# BM_Input_Stage.net
KiCad netlist of a schematic drawn in Altium Designer
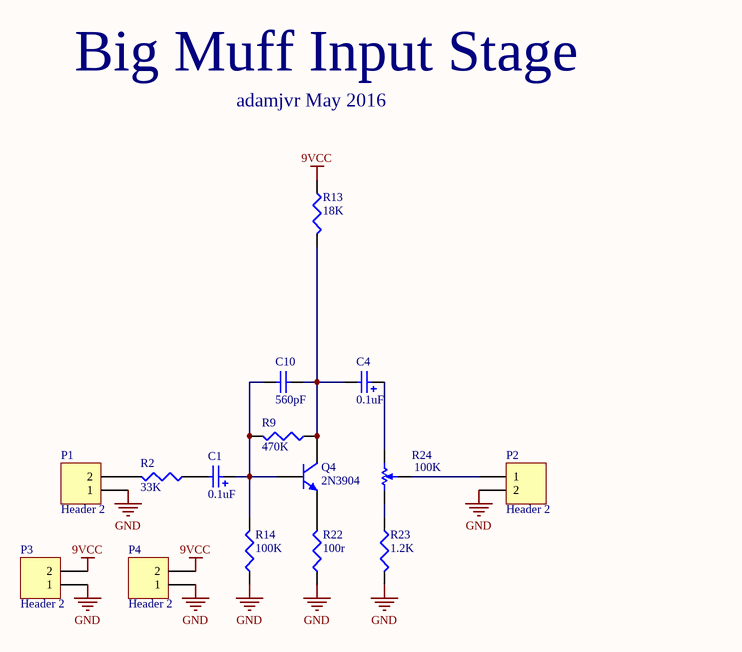
[diagram p0: BM Input Stage.SchDoc]

(export (version "E")
  (design (tool "Eeschema 10.0.6"))
  (components
    (comp (ref "C1")
      (value "0.1uF")
      (footprint "5X12.5mmCAP")
      (description "CAP ALUM 0.1UF 20% 100V RADIAL")
      (fields
        (field (name "MFR") "Nichicon")
        (field (name "TOLERANCE") "20%")
        (field (name "DESIGNER") "Adam Vadala-Roth")
      )
      (libsource (lib "AudioPartLib") (part "UFG2A0R1MDM1TD"))
    )
    (comp (ref "C4")
      (value "0.1uF")
      (footprint "5X12.5mmCAP")
      (description "CAP ALUM 0.1UF 20% 100V RADIAL")
      (fields
        (field (name "MFR") "Nichicon")
        (field (name "TOLERANCE") "20%")
        (field (name "DESIGNER") "Adam Vadala-Roth")
      )
      (libsource (lib "AudioPartLib") (part "UFG2A0R1MDM1TD"))
    )
    (comp (ref "C10")
      (value "560pF")
      (footprint "C0805")
      (fields
        (field (name "MFR") "Samsung-Electro-Mechanics-America,-Inc.")
        (field (name "TOLERANCE") "5%")
        (field (name "VOLTAGE") "50V")
        (field (name "DESIGNER") "Adam Vadala-Roth")
      )
      (libsource (lib "AudioPartLib") (part "CL21C561JBANNNC"))
    )
    (comp (ref "P1")
      (value "Header 2")
      (footprint "HDR1X2")
      (description "Header, 2-Pin")
      (fields (field (name "PUBLISHER") "Altium Limited"))
      (libsource (lib "Miscellaneous Connectors") (part "Header 2"))
    )
    (comp (ref "P2")
      (value "Header 2")
      (footprint "HDR1X2")
      (description "Header, 2-Pin")
      (fields (field (name "PUBLISHER") "Altium Limited"))
      (libsource (lib "") (part "Header 2_1"))
    )
    (comp (ref "P3")
      (value "Header 2")
      (footprint "HDR1X2")
      (description "Header, 2-Pin")
      (fields (field (name "PUBLISHER") "Altium Limited"))
      (libsource (lib "Miscellaneous Connectors") (part "Header 2"))
    )
    (comp (ref "P4")
      (value "Header 2")
      (footprint "HDR1X2")
      (description "Header, 2-Pin")
      (fields (field (name "PUBLISHER") "Altium Limited"))
      (libsource (lib "Miscellaneous Connectors") (part "Header 2"))
    )
    (comp (ref "Q4")
      (value "2N3904")
      (footprint "TO-92A")
      (description "TRANS NPN 40V 0.2A TO-92")
      (fields
        (field (name "MFR") "Fairchild-Semiconductor")
        (field (name "VOLTAGE") "40V")
        (field (name "DESIGNER") "Adam Vadala-Roth")
      )
      (libsource (lib "AudioPartLib") (part "2N3904TF"))
    )
    (comp (ref "R2")
      (value "33K")
      (footprint "R0805")
      (description "RES SMD 33K OHM 1% 1/8W 0805")
      (fields
        (field (name "MFR") "Panasonic-Electronic-Components")
        (field (name "TOLERANCE") "1%")
        (field (name "DESIGNER") "Adam Vadala-Roth")
      )
      (libsource (lib "AudioPartLib") (part "ERJ-6ENF3302V"))
    )
    (comp (ref "R9")
      (value "470K")
      (footprint "R0805")
      (description "RES SMD 470K OHM 1% 1/8W 0805")
      (fields
        (field (name "MFR") "Panasonic-Electronic-Components")
        (field (name "TOLERANCE") "1%")
        (field (name "DESIGNER") "Adam Vadala-Roth")
      )
      (libsource (lib "AudioPartLib") (part "ERJ-6ENF4703V"))
    )
    (comp (ref "R13")
      (value "18K")
      (footprint "R0805")
      (description "RES SMD 18K OHM 1% 1/8W 0805")
      (fields
        (field (name "MFR") "Panasonic-Electronic-Components")
        (field (name "TOLERANCE") "1%")
        (field (name "DESIGNER") "Adam Vadala-Roth")
      )
      (libsource (lib "AudioPartLib") (part "ERJ-6ENF1802V"))
    )
    (comp (ref "R14")
      (value "100K")
      (footprint "R0805")
      (description "RES SMD 100K OHM 1% 1/8W 0805")
      (fields
        (field (name "MFR") "Panasonic-Electronic-Components")
        (field (name "TOLERANCE") "1%")
        (field (name "DESIGNER") "Adam Vadala-Roth")
      )
      (libsource (lib "AudioPartLib") (part "ERJ-6ENF1003V"))
    )
    (comp (ref "R22")
      (value "100r")
      (footprint "R0805")
      (description "RES SMD 100 OHM 1% 1/8W 0805")
      (fields
        (field (name "MFR") "Vishay-Dale")
        (field (name "TOLERANCE") "1%")
        (field (name "DESIGNER") "Adam Vadala-Roth")
      )
      (libsource (lib "AudioPartLib") (part "CRCW0805100RFKEA"))
    )
    (comp (ref "R23")
      (value "1.2K")
      (footprint "R0805")
      (description "RES SMD 1.2K OHM 1% 1/8W 0805")
      (fields
        (field (name "MFR") "Panasonic-Electronic-Components")
        (field (name "TOLERANCE") "1%")
        (field (name "DESIGNER") "Adam Vadala-Roth")
      )
      (libsource (lib "AudioPartLib") (part "ERJ-6ENF1201V"))
    )
    (comp (ref "R24")
      (value "100K")
      (footprint "BOURNS_PTD90SERIES_POT")
      (description "POT 100K OHM 1/20W CARBON LINEAR")
      (fields
        (field (name "MFR") "Bourns Inc.")
        (field (name "TOLERANCE") "20%")
        (field (name "DESIGNER") "Adam Vadala-Roth")
      )
      (libsource (lib "AudioPartLib") (part "PTD901-2015K-B104"))
    )
  )
  (nets
    (net (code "1") (name "9VCC") (class "Default")
      (node (ref "P3") (pin "2") (pinfunction "2_2") (pintype "passive"))
      (node (ref "P4") (pin "2") (pinfunction "2_2") (pintype "passive"))
      (node (ref "R13") (pin "1") (pinfunction "1_1") (pintype "passive"))
    )
    (net (code "2") (name "GND") (class "Default")
      (node (ref "P1") (pin "1") (pinfunction "1_1") (pintype "passive"))
      (node (ref "P2") (pin "2") (pinfunction "2_2") (pintype "passive"))
      (node (ref "P3") (pin "1") (pinfunction "1_1") (pintype "passive"))
      (node (ref "P4") (pin "1") (pinfunction "1_1") (pintype "passive"))
      (node (ref "R14") (pin "1") (pinfunction "1_1") (pintype "passive"))
      (node (ref "R22") (pin "1") (pinfunction "1_1") (pintype "passive"))
      (node (ref "R23") (pin "2") (pinfunction "2_2") (pintype "passive"))
    )
    (net (code "3") (name "Net-(C1-Pad2)") (class "Default")
      (node (ref "C1") (pin "2") (pinfunction "2_2") (pintype "passive"))
      (node (ref "R2") (pin "1") (pinfunction "1_1") (pintype "passive"))
    )
    (net (code "4") (name "Net-(C4-Pad1)") (class "Default")
      (node (ref "C4") (pin "1") (pinfunction "1_1") (pintype "passive"))
      (node (ref "R24") (pin "1") (pinfunction "1_1") (pintype "passive"))
    )
    (net (code "5") (name "Net-(P1-Pad2)") (class "Default")
      (node (ref "P1") (pin "2") (pinfunction "2_2") (pintype "passive"))
      (node (ref "R2") (pin "2") (pinfunction "2_2") (pintype "passive"))
    )
    (net (code "6") (name "Net-(P2-Pad1)") (class "Default")
      (node (ref "P2") (pin "1") (pinfunction "1_1") (pintype "passive"))
      (node (ref "R24") (pin "2") (pinfunction "2_2") (pintype "passive"))
    )
    (net (code "7") (name "Net-(Q4-B)") (class "Default")
      (node (ref "C1") (pin "1") (pinfunction "1_1") (pintype "passive"))
      (node (ref "C10") (pin "2") (pinfunction "2_2") (pintype "passive"))
      (node (ref "Q4") (pin "2") (pinfunction "B_2") (pintype "passive"))
      (node (ref "R14") (pin "2") (pinfunction "2_2") (pintype "passive"))
      (node (ref "R9") (pin "2") (pinfunction "2_2") (pintype "passive"))
    )
    (net (code "8") (name "Net-(Q4-C)") (class "Default")
      (node (ref "C10") (pin "1") (pinfunction "1_1") (pintype "passive"))
      (node (ref "C4") (pin "2") (pinfunction "2_2") (pintype "passive"))
      (node (ref "Q4") (pin "3") (pinfunction "C_3") (pintype "passive"))
      (node (ref "R13") (pin "2") (pinfunction "2_2") (pintype "passive"))
      (node (ref "R9") (pin "1") (pinfunction "1_1") (pintype "passive"))
    )
    (net (code "9") (name "Net-(Q4-E)") (class "Default")
      (node (ref "Q4") (pin "1") (pinfunction "E_1") (pintype "passive"))
      (node (ref "R22") (pin "2") (pinfunction "2_2") (pintype "passive"))
    )
    (net (code "10") (name "Net-(R23-Pad1)") (class "Default")
      (node (ref "R23") (pin "1") (pinfunction "1_1") (pintype "passive"))
      (node (ref "R24") (pin "3") (pinfunction "3_3") (pintype "passive"))
    )
  )
)
